# NixiTubeClock.net
KiCad netlist of a schematic drawn in EAGLE
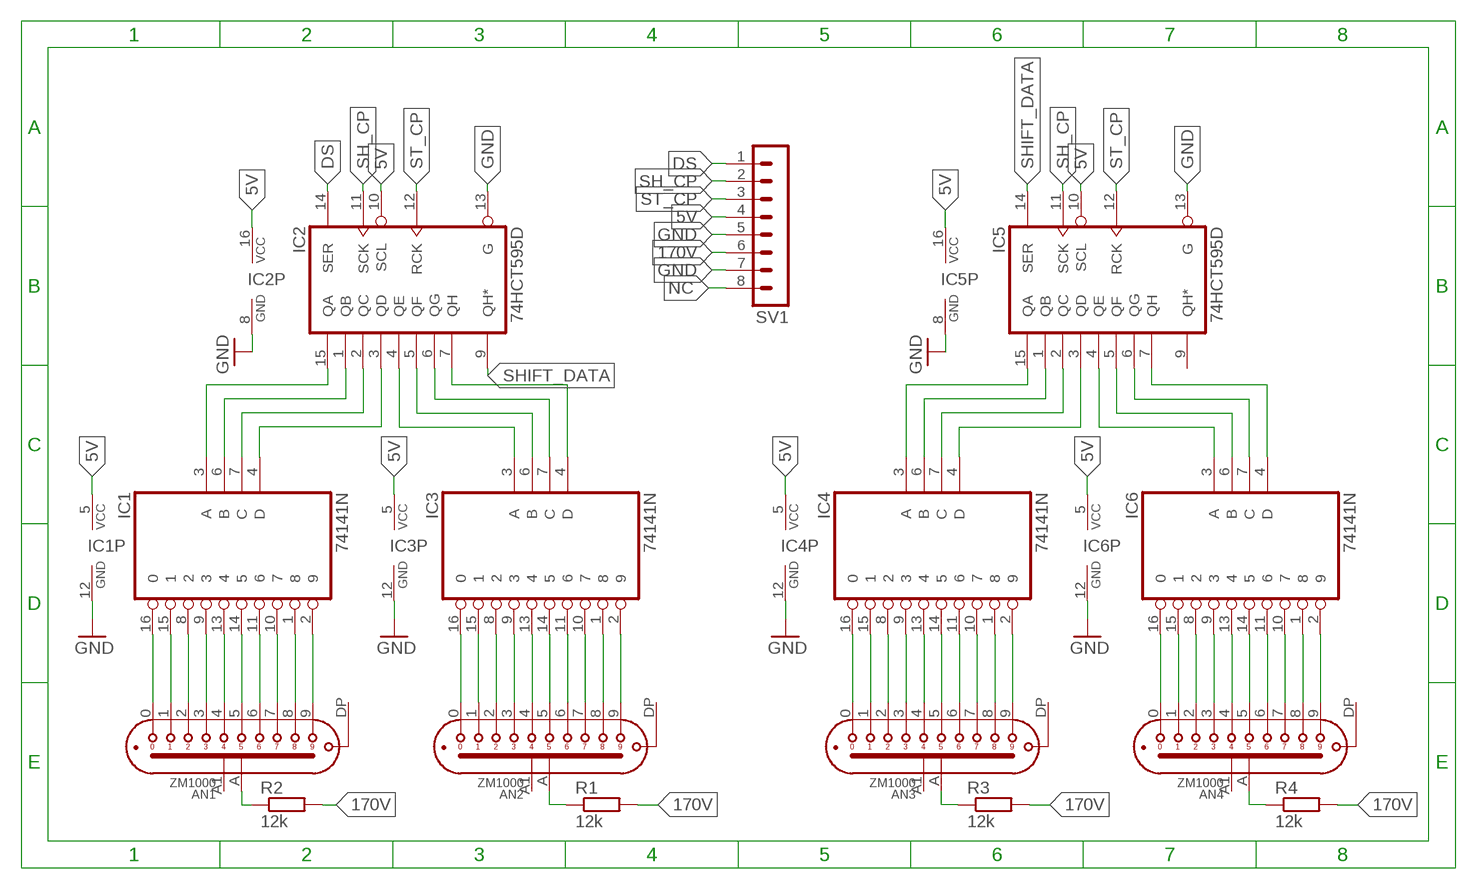
[diagram p0: schematic, sheet 1]
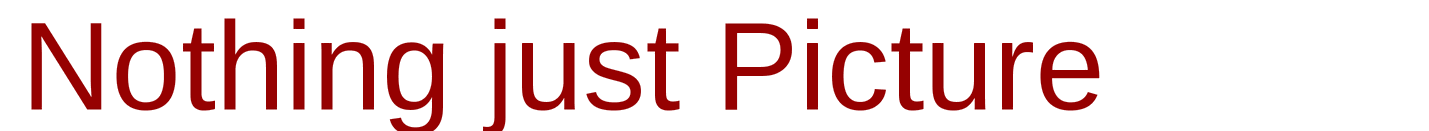
[diagram p1: schematic, sheet 2]

(export (version "E")
  (design (tool "Eeschema 10.0.6"))
  (components
    (comp (ref "AN1")
      (value "ZM1000")
      (footprint "eagle-import:ZM1000")
      (libsource (lib "eagle-import") (part "ZM1000"))
    )
    (comp (ref "AN2")
      (value "ZM1000")
      (footprint "eagle-import:ZM1000")
      (libsource (lib "eagle-import") (part "ZM1000"))
    )
    (comp (ref "AN3")
      (value "ZM1000")
      (footprint "eagle-import:ZM1000")
      (libsource (lib "eagle-import") (part "ZM1000"))
    )
    (comp (ref "AN4")
      (value "ZM1000")
      (footprint "eagle-import:ZM1000")
      (libsource (lib "eagle-import") (part "ZM1000"))
    )
    (comp (ref "IC1")
      (value "74141N")
      (footprint "eagle-import:DIL16")
      (libsource (lib "eagle-import") (part "74141N"))
    )
    (comp (ref "IC2")
      (value "74HCT595D")
      (footprint "eagle-import:SO16")
      (libsource (lib "eagle-import") (part "74595DHCT"))
    )
    (comp (ref "IC3")
      (value "74141N")
      (footprint "eagle-import:DIL16")
      (libsource (lib "eagle-import") (part "74141N"))
    )
    (comp (ref "IC4")
      (value "74141N")
      (footprint "eagle-import:DIL16")
      (libsource (lib "eagle-import") (part "74141N"))
    )
    (comp (ref "IC5")
      (value "74HCT595D")
      (footprint "eagle-import:SO16")
      (libsource (lib "eagle-import") (part "74595DHCT"))
    )
    (comp (ref "IC6")
      (value "74141N")
      (footprint "eagle-import:DIL16")
      (libsource (lib "eagle-import") (part "74141N"))
    )
    (comp (ref "R1")
      (value "12k")
      (footprint "eagle-import:R1206")
      (libsource (lib "eagle-import") (part "R-EU_1206R1206"))
    )
    (comp (ref "R2")
      (value "12k")
      (footprint "eagle-import:R1206")
      (libsource (lib "eagle-import") (part "R-EU_1206R1206"))
    )
    (comp (ref "R3")
      (value "12k")
      (footprint "eagle-import:R1206")
      (libsource (lib "eagle-import") (part "R-EU_1206R1206"))
    )
    (comp (ref "R4")
      (value "12k")
      (footprint "eagle-import:R1206")
      (libsource (lib "eagle-import") (part "R-EU_1206R1206"))
    )
    (comp (ref "SV1")
      (value "MA08-1")
      (footprint "eagle-import:MA08-1")
      (libsource (lib "eagle-import") (part "MA08-1"))
    )
  )
  (nets
    (net (code "1") (name "5V") (class "Default")
      (node (ref "IC1") (pin "5") (pinfunction "VCC_5") (pintype "power_in"))
      (node (ref "IC2") (pin "10") (pinfunction "SCL_10") (pintype "input"))
      (node (ref "IC2") (pin "16") (pinfunction "VCC_16") (pintype "power_in"))
      (node (ref "IC3") (pin "5") (pinfunction "VCC_5") (pintype "power_in"))
      (node (ref "IC4") (pin "5") (pinfunction "VCC_5") (pintype "power_in"))
      (node (ref "IC5") (pin "10") (pinfunction "SCL_10") (pintype "input"))
      (node (ref "IC5") (pin "16") (pinfunction "VCC_16") (pintype "power_in"))
      (node (ref "IC6") (pin "5") (pinfunction "VCC_5") (pintype "power_in"))
      (node (ref "SV1") (pin "4") (pinfunction "4_4") (pintype "passive"))
    )
    (net (code "2") (name "170V") (class "Default")
      (node (ref "R1") (pin "2") (pinfunction "2_2") (pintype "passive"))
      (node (ref "R2") (pin "2") (pinfunction "2_2") (pintype "passive"))
      (node (ref "R3") (pin "2") (pinfunction "2_2") (pintype "passive"))
      (node (ref "R4") (pin "2") (pinfunction "2_2") (pintype "passive"))
      (node (ref "SV1") (pin "6") (pinfunction "6_6") (pintype "passive"))
    )
    (net (code "3") (name "DS") (class "Default")
      (node (ref "IC2") (pin "14") (pinfunction "SER_14") (pintype "input"))
      (node (ref "SV1") (pin "1") (pinfunction "1_1") (pintype "passive"))
    )
    (net (code "4") (name "GND") (class "Default")
      (node (ref "IC1") (pin "12") (pinfunction "GND_12") (pintype "power_in"))
      (node (ref "IC2") (pin "13") (pinfunction "G_13") (pintype "input"))
      (node (ref "IC2") (pin "8") (pinfunction "GND_8") (pintype "power_in"))
      (node (ref "IC3") (pin "12") (pinfunction "GND_12") (pintype "power_in"))
      (node (ref "IC4") (pin "12") (pinfunction "GND_12") (pintype "power_in"))
      (node (ref "IC5") (pin "13") (pinfunction "G_13") (pintype "input"))
      (node (ref "IC5") (pin "8") (pinfunction "GND_8") (pintype "power_in"))
      (node (ref "IC6") (pin "12") (pinfunction "GND_12") (pintype "power_in"))
      (node (ref "SV1") (pin "5") (pinfunction "5_5") (pintype "passive"))
      (node (ref "SV1") (pin "7") (pinfunction "7_7") (pintype "passive"))
    )
    (net (code "5") (name "NC") (class "Default")
      (node (ref "SV1") (pin "8") (pinfunction "8_8") (pintype "passive"))
    )
    (net (code "6") (name "Net-(AN1-A1)") (class "Default")
      (node (ref "AN1") (pin "A") (pinfunction "A1_A") (pintype "passive"))
      (node (ref "R2") (pin "1") (pinfunction "1_1") (pintype "passive"))
    )
    (net (code "7") (name "Net-(AN2-A1)") (class "Default")
      (node (ref "AN2") (pin "A") (pinfunction "A1_A") (pintype "passive"))
      (node (ref "R1") (pin "1") (pinfunction "1_1") (pintype "passive"))
    )
    (net (code "8") (name "Net-(AN3-A1)") (class "Default")
      (node (ref "AN3") (pin "A") (pinfunction "A1_A") (pintype "passive"))
      (node (ref "R3") (pin "1") (pinfunction "1_1") (pintype "passive"))
    )
    (net (code "9") (name "Net-(AN4-A1)") (class "Default")
      (node (ref "AN4") (pin "A") (pinfunction "A1_A") (pintype "passive"))
      (node (ref "R4") (pin "1") (pinfunction "1_1") (pintype "passive"))
    )
    (net (code "10") (name "Net-(IC1A-0)") (class "Default")
      (node (ref "AN1") (pin "0") (pinfunction "0_0") (pintype "passive"))
      (node (ref "IC1") (pin "16") (pinfunction "0_16") (pintype "open_collector"))
    )
    (net (code "11") (name "Net-(IC1A-1)") (class "Default")
      (node (ref "AN1") (pin "1") (pinfunction "1_1") (pintype "passive"))
      (node (ref "IC1") (pin "15") (pinfunction "1_15") (pintype "open_collector"))
    )
    (net (code "12") (name "Net-(IC1A-2)") (class "Default")
      (node (ref "AN1") (pin "2") (pinfunction "2_2") (pintype "passive"))
      (node (ref "IC1") (pin "8") (pinfunction "2_8") (pintype "open_collector"))
    )
    (net (code "13") (name "Net-(IC1A-3)") (class "Default")
      (node (ref "AN1") (pin "3") (pinfunction "3_3") (pintype "passive"))
      (node (ref "IC1") (pin "9") (pinfunction "3_9") (pintype "open_collector"))
    )
    (net (code "14") (name "Net-(IC1A-4)") (class "Default")
      (node (ref "AN1") (pin "4") (pinfunction "4_4") (pintype "passive"))
      (node (ref "IC1") (pin "13") (pinfunction "4_13") (pintype "open_collector"))
    )
    (net (code "15") (name "Net-(IC1A-5)") (class "Default")
      (node (ref "AN1") (pin "5") (pinfunction "5_5") (pintype "passive"))
      (node (ref "IC1") (pin "14") (pinfunction "5_14") (pintype "open_collector"))
    )
    (net (code "16") (name "Net-(IC1A-6)") (class "Default")
      (node (ref "AN1") (pin "6") (pinfunction "6_6") (pintype "passive"))
      (node (ref "IC1") (pin "11") (pinfunction "6_11") (pintype "open_collector"))
    )
    (net (code "17") (name "Net-(IC1A-7)") (class "Default")
      (node (ref "AN1") (pin "7") (pinfunction "7_7") (pintype "passive"))
      (node (ref "IC1") (pin "10") (pinfunction "7_10") (pintype "open_collector"))
    )
    (net (code "18") (name "Net-(IC1A-8)") (class "Default")
      (node (ref "AN1") (pin "8") (pinfunction "8_8") (pintype "passive"))
      (node (ref "IC1") (pin "1") (pinfunction "8_1") (pintype "open_collector"))
    )
    (net (code "19") (name "Net-(IC1A-9)") (class "Default")
      (node (ref "AN1") (pin "9") (pinfunction "9_9") (pintype "passive"))
      (node (ref "IC1") (pin "2") (pinfunction "9_2") (pintype "open_collector"))
    )
    (net (code "20") (name "Net-(IC1A-A)") (class "Default")
      (node (ref "IC1") (pin "3") (pinfunction "A_3") (pintype "input"))
      (node (ref "IC2") (pin "15") (pinfunction "QA_15") (pintype "tri_state"))
    )
    (net (code "21") (name "Net-(IC1A-B)") (class "Default")
      (node (ref "IC1") (pin "6") (pinfunction "B_6") (pintype "input"))
      (node (ref "IC2") (pin "1") (pinfunction "QB_1") (pintype "tri_state"))
    )
    (net (code "22") (name "Net-(IC1A-C)") (class "Default")
      (node (ref "IC1") (pin "7") (pinfunction "C_7") (pintype "input"))
      (node (ref "IC2") (pin "2") (pinfunction "QC_2") (pintype "tri_state"))
    )
    (net (code "23") (name "Net-(IC1A-D)") (class "Default")
      (node (ref "IC1") (pin "4") (pinfunction "D_4") (pintype "input"))
      (node (ref "IC2") (pin "3") (pinfunction "QD_3") (pintype "tri_state"))
    )
    (net (code "24") (name "Net-(IC2A-QE)") (class "Default")
      (node (ref "IC2") (pin "4") (pinfunction "QE_4") (pintype "tri_state"))
      (node (ref "IC3") (pin "3") (pinfunction "A_3") (pintype "input"))
    )
    (net (code "25") (name "Net-(IC2A-QF)") (class "Default")
      (node (ref "IC2") (pin "5") (pinfunction "QF_5") (pintype "tri_state"))
      (node (ref "IC3") (pin "6") (pinfunction "B_6") (pintype "input"))
    )
    (net (code "26") (name "Net-(IC2A-QG)") (class "Default")
      (node (ref "IC2") (pin "6") (pinfunction "QG_6") (pintype "tri_state"))
      (node (ref "IC3") (pin "7") (pinfunction "C_7") (pintype "input"))
    )
    (net (code "27") (name "Net-(IC2A-QH)") (class "Default")
      (node (ref "IC2") (pin "7") (pinfunction "QH_7") (pintype "tri_state"))
      (node (ref "IC3") (pin "4") (pinfunction "D_4") (pintype "input"))
    )
    (net (code "28") (name "Net-(IC3A-0)") (class "Default")
      (node (ref "AN2") (pin "0") (pinfunction "0_0") (pintype "passive"))
      (node (ref "IC3") (pin "16") (pinfunction "0_16") (pintype "open_collector"))
    )
    (net (code "29") (name "Net-(IC3A-1)") (class "Default")
      (node (ref "AN2") (pin "1") (pinfunction "1_1") (pintype "passive"))
      (node (ref "IC3") (pin "15") (pinfunction "1_15") (pintype "open_collector"))
    )
    (net (code "30") (name "Net-(IC3A-2)") (class "Default")
      (node (ref "AN2") (pin "2") (pinfunction "2_2") (pintype "passive"))
      (node (ref "IC3") (pin "8") (pinfunction "2_8") (pintype "open_collector"))
    )
    (net (code "31") (name "Net-(IC3A-3)") (class "Default")
      (node (ref "AN2") (pin "3") (pinfunction "3_3") (pintype "passive"))
      (node (ref "IC3") (pin "9") (pinfunction "3_9") (pintype "open_collector"))
    )
    (net (code "32") (name "Net-(IC3A-4)") (class "Default")
      (node (ref "AN2") (pin "4") (pinfunction "4_4") (pintype "passive"))
      (node (ref "IC3") (pin "13") (pinfunction "4_13") (pintype "open_collector"))
    )
    (net (code "33") (name "Net-(IC3A-5)") (class "Default")
      (node (ref "AN2") (pin "5") (pinfunction "5_5") (pintype "passive"))
      (node (ref "IC3") (pin "14") (pinfunction "5_14") (pintype "open_collector"))
    )
    (net (code "34") (name "Net-(IC3A-6)") (class "Default")
      (node (ref "AN2") (pin "6") (pinfunction "6_6") (pintype "passive"))
      (node (ref "IC3") (pin "11") (pinfunction "6_11") (pintype "open_collector"))
    )
    (net (code "35") (name "Net-(IC3A-7)") (class "Default")
      (node (ref "AN2") (pin "7") (pinfunction "7_7") (pintype "passive"))
      (node (ref "IC3") (pin "10") (pinfunction "7_10") (pintype "open_collector"))
    )
    (net (code "36") (name "Net-(IC3A-8)") (class "Default")
      (node (ref "AN2") (pin "8") (pinfunction "8_8") (pintype "passive"))
      (node (ref "IC3") (pin "1") (pinfunction "8_1") (pintype "open_collector"))
    )
    (net (code "37") (name "Net-(IC3A-9)") (class "Default")
      (node (ref "AN2") (pin "9") (pinfunction "9_9") (pintype "passive"))
      (node (ref "IC3") (pin "2") (pinfunction "9_2") (pintype "open_collector"))
    )
    (net (code "38") (name "Net-(IC4A-0)") (class "Default")
      (node (ref "AN3") (pin "0") (pinfunction "0_0") (pintype "passive"))
      (node (ref "IC4") (pin "16") (pinfunction "0_16") (pintype "open_collector"))
    )
    (net (code "39") (name "Net-(IC4A-1)") (class "Default")
      (node (ref "AN3") (pin "1") (pinfunction "1_1") (pintype "passive"))
      (node (ref "IC4") (pin "15") (pinfunction "1_15") (pintype "open_collector"))
    )
    (net (code "40") (name "Net-(IC4A-2)") (class "Default")
      (node (ref "AN3") (pin "2") (pinfunction "2_2") (pintype "passive"))
      (node (ref "IC4") (pin "8") (pinfunction "2_8") (pintype "open_collector"))
    )
    (net (code "41") (name "Net-(IC4A-3)") (class "Default")
      (node (ref "AN3") (pin "3") (pinfunction "3_3") (pintype "passive"))
      (node (ref "IC4") (pin "9") (pinfunction "3_9") (pintype "open_collector"))
    )
    (net (code "42") (name "Net-(IC4A-4)") (class "Default")
      (node (ref "AN3") (pin "4") (pinfunction "4_4") (pintype "passive"))
      (node (ref "IC4") (pin "13") (pinfunction "4_13") (pintype "open_collector"))
    )
    (net (code "43") (name "Net-(IC4A-5)") (class "Default")
      (node (ref "AN3") (pin "5") (pinfunction "5_5") (pintype "passive"))
      (node (ref "IC4") (pin "14") (pinfunction "5_14") (pintype "open_collector"))
    )
    (net (code "44") (name "Net-(IC4A-6)") (class "Default")
      (node (ref "AN3") (pin "6") (pinfunction "6_6") (pintype "passive"))
      (node (ref "IC4") (pin "11") (pinfunction "6_11") (pintype "open_collector"))
    )
    (net (code "45") (name "Net-(IC4A-7)") (class "Default")
      (node (ref "AN3") (pin "7") (pinfunction "7_7") (pintype "passive"))
      (node (ref "IC4") (pin "10") (pinfunction "7_10") (pintype "open_collector"))
    )
    (net (code "46") (name "Net-(IC4A-8)") (class "Default")
      (node (ref "AN3") (pin "8") (pinfunction "8_8") (pintype "passive"))
      (node (ref "IC4") (pin "1") (pinfunction "8_1") (pintype "open_collector"))
    )
    (net (code "47") (name "Net-(IC4A-9)") (class "Default")
      (node (ref "AN3") (pin "9") (pinfunction "9_9") (pintype "passive"))
      (node (ref "IC4") (pin "2") (pinfunction "9_2") (pintype "open_collector"))
    )
    (net (code "48") (name "Net-(IC4A-A)") (class "Default")
      (node (ref "IC4") (pin "3") (pinfunction "A_3") (pintype "input"))
      (node (ref "IC5") (pin "15") (pinfunction "QA_15") (pintype "tri_state"))
    )
    (net (code "49") (name "Net-(IC4A-B)") (class "Default")
      (node (ref "IC4") (pin "6") (pinfunction "B_6") (pintype "input"))
      (node (ref "IC5") (pin "1") (pinfunction "QB_1") (pintype "tri_state"))
    )
    (net (code "50") (name "Net-(IC4A-C)") (class "Default")
      (node (ref "IC4") (pin "7") (pinfunction "C_7") (pintype "input"))
      (node (ref "IC5") (pin "2") (pinfunction "QC_2") (pintype "tri_state"))
    )
    (net (code "51") (name "Net-(IC4A-D)") (class "Default")
      (node (ref "IC4") (pin "4") (pinfunction "D_4") (pintype "input"))
      (node (ref "IC5") (pin "3") (pinfunction "QD_3") (pintype "tri_state"))
    )
    (net (code "52") (name "Net-(IC5A-QE)") (class "Default")
      (node (ref "IC5") (pin "4") (pinfunction "QE_4") (pintype "tri_state"))
      (node (ref "IC6") (pin "3") (pinfunction "A_3") (pintype "input"))
    )
    (net (code "53") (name "Net-(IC5A-QF)") (class "Default")
      (node (ref "IC5") (pin "5") (pinfunction "QF_5") (pintype "tri_state"))
      (node (ref "IC6") (pin "6") (pinfunction "B_6") (pintype "input"))
    )
    (net (code "54") (name "Net-(IC5A-QG)") (class "Default")
      (node (ref "IC5") (pin "6") (pinfunction "QG_6") (pintype "tri_state"))
      (node (ref "IC6") (pin "7") (pinfunction "C_7") (pintype "input"))
    )
    (net (code "55") (name "Net-(IC5A-QH)") (class "Default")
      (node (ref "IC5") (pin "7") (pinfunction "QH_7") (pintype "tri_state"))
      (node (ref "IC6") (pin "4") (pinfunction "D_4") (pintype "input"))
    )
    (net (code "56") (name "Net-(IC6A-0)") (class "Default")
      (node (ref "AN4") (pin "0") (pinfunction "0_0") (pintype "passive"))
      (node (ref "IC6") (pin "16") (pinfunction "0_16") (pintype "open_collector"))
    )
    (net (code "57") (name "Net-(IC6A-1)") (class "Default")
      (node (ref "AN4") (pin "1") (pinfunction "1_1") (pintype "passive"))
      (node (ref "IC6") (pin "15") (pinfunction "1_15") (pintype "open_collector"))
    )
    (net (code "58") (name "Net-(IC6A-2)") (class "Default")
      (node (ref "AN4") (pin "2") (pinfunction "2_2") (pintype "passive"))
      (node (ref "IC6") (pin "8") (pinfunction "2_8") (pintype "open_collector"))
    )
    (net (code "59") (name "Net-(IC6A-3)") (class "Default")
      (node (ref "AN4") (pin "3") (pinfunction "3_3") (pintype "passive"))
      (node (ref "IC6") (pin "9") (pinfunction "3_9") (pintype "open_collector"))
    )
    (net (code "60") (name "Net-(IC6A-4)") (class "Default")
      (node (ref "AN4") (pin "4") (pinfunction "4_4") (pintype "passive"))
      (node (ref "IC6") (pin "13") (pinfunction "4_13") (pintype "open_collector"))
    )
    (net (code "61") (name "Net-(IC6A-5)") (class "Default")
      (node (ref "AN4") (pin "5") (pinfunction "5_5") (pintype "passive"))
      (node (ref "IC6") (pin "14") (pinfunction "5_14") (pintype "open_collector"))
    )
    (net (code "62") (name "Net-(IC6A-6)") (class "Default")
      (node (ref "AN4") (pin "6") (pinfunction "6_6") (pintype "passive"))
      (node (ref "IC6") (pin "11") (pinfunction "6_11") (pintype "open_collector"))
    )
    (net (code "63") (name "Net-(IC6A-7)") (class "Default")
      (node (ref "AN4") (pin "7") (pinfunction "7_7") (pintype "passive"))
      (node (ref "IC6") (pin "10") (pinfunction "7_10") (pintype "open_collector"))
    )
    (net (code "64") (name "Net-(IC6A-8)") (class "Default")
      (node (ref "AN4") (pin "8") (pinfunction "8_8") (pintype "passive"))
      (node (ref "IC6") (pin "1") (pinfunction "8_1") (pintype "open_collector"))
    )
    (net (code "65") (name "Net-(IC6A-9)") (class "Default")
      (node (ref "AN4") (pin "9") (pinfunction "9_9") (pintype "passive"))
      (node (ref "IC6") (pin "2") (pinfunction "9_2") (pintype "open_collector"))
    )
    (net (code "66") (name "SHIFT_DATA") (class "Default")
      (node (ref "IC2") (pin "9") (pinfunction "QH*_9") (pintype "tri_state"))
      (node (ref "IC5") (pin "14") (pinfunction "SER_14") (pintype "input"))
    )
    (net (code "67") (name "SH_CP") (class "Default")
      (node (ref "IC2") (pin "11") (pinfunction "SCK_11") (pintype "input"))
      (node (ref "IC5") (pin "11") (pinfunction "SCK_11") (pintype "input"))
      (node (ref "SV1") (pin "2") (pinfunction "2_2") (pintype "passive"))
    )
    (net (code "68") (name "ST_CP") (class "Default")
      (node (ref "IC2") (pin "12") (pinfunction "RCK_12") (pintype "input"))
      (node (ref "IC5") (pin "12") (pinfunction "RCK_12") (pintype "input"))
      (node (ref "SV1") (pin "3") (pinfunction "3_3") (pintype "passive"))
    )
    (net (code "69") (name "unconnected-(AN1-A2-PadA1)") (class "Default")
      (node (ref "AN1") (pin "A1") (pinfunction "A2_A1") (pintype "passive"))
    )
    (net (code "70") (name "unconnected-(AN1-DPL-PadDP)") (class "Default")
      (node (ref "AN1") (pin "DP") (pinfunction "DPL_DP") (pintype "passive"))
    )
    (net (code "71") (name "unconnected-(AN2-A2-PadA1)") (class "Default")
      (node (ref "AN2") (pin "A1") (pinfunction "A2_A1") (pintype "passive"))
    )
    (net (code "72") (name "unconnected-(AN2-DPL-PadDP)") (class "Default")
      (node (ref "AN2") (pin "DP") (pinfunction "DPL_DP") (pintype "passive"))
    )
    (net (code "73") (name "unconnected-(AN3-A2-PadA1)") (class "Default")
      (node (ref "AN3") (pin "A1") (pinfunction "A2_A1") (pintype "passive"))
    )
    (net (code "74") (name "unconnected-(AN3-DPL-PadDP)") (class "Default")
      (node (ref "AN3") (pin "DP") (pinfunction "DPL_DP") (pintype "passive"))
    )
    (net (code "75") (name "unconnected-(AN4-A2-PadA1)") (class "Default")
      (node (ref "AN4") (pin "A1") (pinfunction "A2_A1") (pintype "passive"))
    )
    (net (code "76") (name "unconnected-(AN4-DPL-PadDP)") (class "Default")
      (node (ref "AN4") (pin "DP") (pinfunction "DPL_DP") (pintype "passive"))
    )
    (net (code "77") (name "unconnected-(IC5A-QH*-Pad9)") (class "Default")
      (node (ref "IC5") (pin "9") (pinfunction "QH*_9") (pintype "tri_state"))
    )
  )
)
